# ConMicSchem.net
KiCad netlist of a schematic drawn in Altium Designer
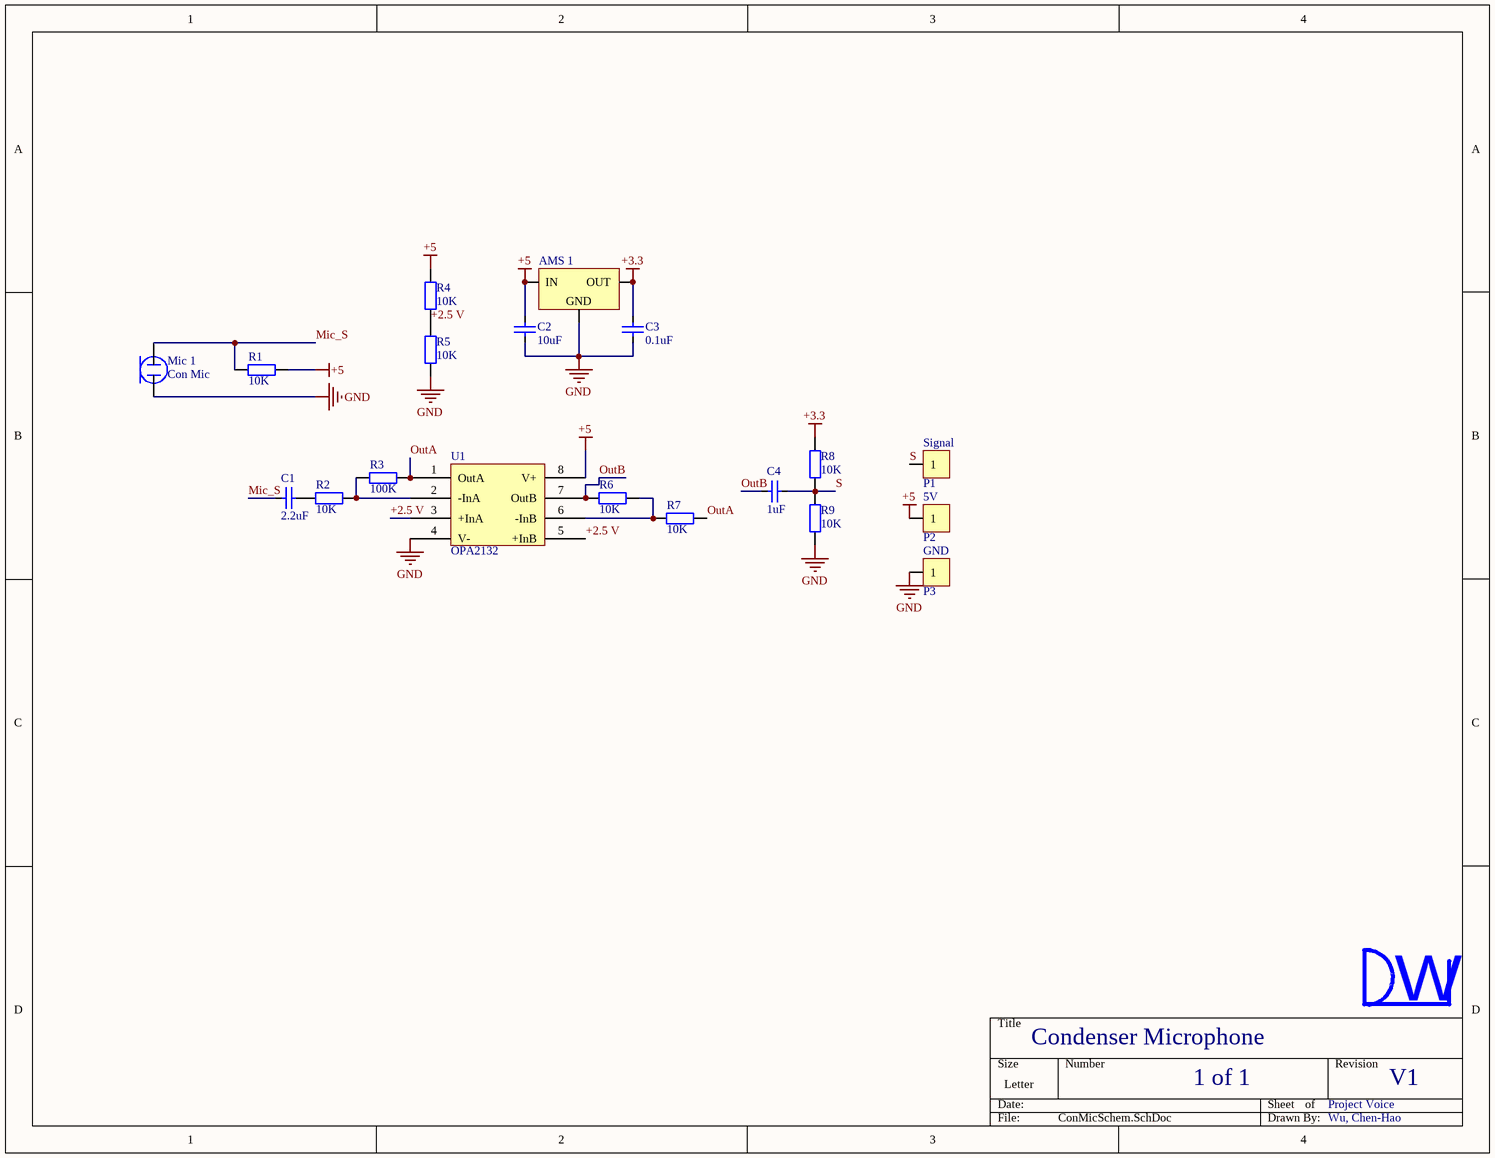
[diagram p0: ConMicSchem.SchDoc]

(export (version "E")
  (design (tool "Eeschema 10.0.6"))
  (components
    (comp (ref "*") (value "DHW_MARK") (libsource (lib "SCH_Mark") (part "DHW_MARK")))
    (comp (ref "AMS 1")
      (value "AMS1117")
      (footprint "PCB_IC:SOT223")
      (description "Power")
      (libsource (lib "SCH_IC") (part "AMS1117"))
    )
    (comp (ref "C1")
      (value "2.2uF")
      (footprint "PCB_Passive:CAP_0603")
      (description "Capacitor")
      (fields (field (name "Comment") "Cap_0603"))
      (libsource (lib "SCH_Passive") (part "Cap_0603"))
    )
    (comp (ref "C2")
      (value "10uF")
      (footprint "PCB_Passive:CAP_0603")
      (description "Capacitor")
      (fields (field (name "Comment") "Cap_0603"))
      (libsource (lib "SCH_Passive") (part "Cap_0603"))
    )
    (comp (ref "C3")
      (value "0.1uF")
      (footprint "PCB_Passive:CAP_0603")
      (description "Capacitor")
      (fields (field (name "Comment") "Cap_0603"))
      (libsource (lib "SCH_Passive") (part "Cap_0603"))
    )
    (comp (ref "C4")
      (value "1uF")
      (footprint "PCB_Passive:CAP_0603")
      (description "Capacitor")
      (fields (field (name "Comment") "Cap_0603"))
      (libsource (lib "SCH_Passive") (part "Cap_0603"))
    )
    (comp (ref "Mic 1")
      (value "Con Mic")
      (footprint "Con_Mic_9.6mm")
      (description "Condenser Microphone")
      (libsource (lib "SCH_Passive") (part "Con_Mic_9.7mm"))
    )
    (comp (ref "P1")
      (value "Signal")
      (footprint "PCB_Connector:HDR1X1_180_2.54")
      (description "Header")
      (libsource (lib "SCH_Connector") (part "HDR1X1_180_2.54"))
    )
    (comp (ref "P2")
      (value "5V")
      (footprint "PCB_Connector:HDR1X1_180_2.54")
      (description "Header")
      (libsource (lib "SCH_Connector") (part "HDR1X1_180_2.54"))
    )
    (comp (ref "P3")
      (value "GND")
      (footprint "PCB_Connector:HDR1X1_180_2.54")
      (description "Header")
      (libsource (lib "SCH_Connector") (part "HDR1X1_180_2.54"))
    )
    (comp (ref "R1")
      (value "10K")
      (footprint "PCB_Passive:RES_0603")
      (description "Resistor")
      (fields (field (name "Comment") "Res_0603"))
      (libsource (lib "SCH_Passive") (part "Res_0603"))
    )
    (comp (ref "R2")
      (value "10K")
      (footprint "PCB_Passive:RES_0603")
      (description "Resistor")
      (fields (field (name "Comment") "Res_0603"))
      (libsource (lib "SCH_Passive") (part "Res_0603"))
    )
    (comp (ref "R3")
      (value "100K")
      (footprint "PCB_Passive:RES_0603")
      (description "Resistor")
      (fields (field (name "Comment") "Res_0603"))
      (libsource (lib "SCH_Passive") (part "Res_0603"))
    )
    (comp (ref "R4")
      (value "10K")
      (footprint "PCB_Passive:RES_0603")
      (description "Resistor")
      (fields (field (name "Comment") "Res_0603"))
      (libsource (lib "") (part "Res_0603_1"))
    )
    (comp (ref "R5")
      (value "10K")
      (footprint "PCB_Passive:RES_0603")
      (description "Resistor")
      (fields (field (name "Comment") "Res_0603"))
      (libsource (lib "") (part "Res_0603_1"))
    )
    (comp (ref "R6")
      (value "10K")
      (footprint "PCB_Passive:RES_0603")
      (description "Resistor")
      (fields (field (name "Comment") "Res_0603"))
      (libsource (lib "SCH_Passive") (part "Res_0603"))
    )
    (comp (ref "R7")
      (value "10K")
      (footprint "PCB_Passive:RES_0603")
      (description "Resistor")
      (fields (field (name "Comment") "Res_0603"))
      (libsource (lib "SCH_Passive") (part "Res_0603"))
    )
    (comp (ref "R8")
      (value "10K")
      (footprint "PCB_Passive:RES_0603")
      (description "Resistor")
      (fields (field (name "Comment") "Res_0603"))
      (libsource (lib "") (part "Res_0603_1"))
    )
    (comp (ref "R9")
      (value "10K")
      (footprint "PCB_Passive:RES_0603")
      (description "Resistor")
      (fields (field (name "Comment") "Res_0603"))
      (libsource (lib "") (part "Res_0603_1"))
    )
    (comp (ref "U1")
      (value "OPA2132")
      (footprint "DIP_8")
      (description "TI BB OPA2132 - 2 op amps IC")
      (libsource (lib "SCH_IC") (part "OPA2132"))
    )
  )
  (nets
    (net (code "1") (name "+3.3") (class "Default")
      (node (ref "AMS 1") (pin "2") (pinfunction "OUT_2") (pintype "power_in"))
      (node (ref "C3") (pin "2") (pinfunction "2_2") (pintype "passive"))
      (node (ref "R8") (pin "2") (pinfunction "2_2") (pintype "passive"))
    )
    (net (code "2") (name "+5") (class "Default")
      (node (ref "AMS 1") (pin "3") (pinfunction "IN_3") (pintype "power_in"))
      (node (ref "C2") (pin "2") (pinfunction "2_2") (pintype "passive"))
      (node (ref "P2") (pin "1") (pinfunction "1_1") (pintype "passive"))
      (node (ref "R1") (pin "2") (pinfunction "2_2") (pintype "passive"))
      (node (ref "R4") (pin "2") (pinfunction "2_2") (pintype "passive"))
      (node (ref "U1") (pin "8") (pinfunction "V+_8") (pintype "passive"))
    )
    (net (code "3") (name "/+2.5 V") (class "Default")
      (node (ref "R4") (pin "1") (pinfunction "1_1") (pintype "passive"))
      (node (ref "R5") (pin "2") (pinfunction "2_2") (pintype "passive"))
      (node (ref "U1") (pin "3") (pinfunction "+InA_3") (pintype "passive"))
      (node (ref "U1") (pin "5") (pinfunction "+InB_5") (pintype "passive"))
    )
    (net (code "4") (name "/Mic_S") (class "Default")
      (node (ref "C1") (pin "1") (pinfunction "1_1") (pintype "passive"))
      (node (ref "Mic 1") (pin "1") (pinfunction "FlexiblePlat_1") (pintype "passive"))
      (node (ref "R1") (pin "1") (pinfunction "1_1") (pintype "passive"))
    )
    (net (code "5") (name "/OutA") (class "Default")
      (node (ref "R3") (pin "2") (pinfunction "2_2") (pintype "passive"))
      (node (ref "R7") (pin "2") (pinfunction "2_2") (pintype "passive"))
      (node (ref "U1") (pin "1") (pinfunction "OutA_1") (pintype "passive"))
    )
    (net (code "6") (name "/OutB") (class "Default")
      (node (ref "C4") (pin "2") (pinfunction "2_2") (pintype "passive"))
      (node (ref "R6") (pin "1") (pinfunction "1_1") (pintype "passive"))
      (node (ref "U1") (pin "7") (pinfunction "OutB_7") (pintype "passive"))
    )
    (net (code "7") (name "/S") (class "Default")
      (node (ref "C4") (pin "1") (pinfunction "1_1") (pintype "passive"))
      (node (ref "P1") (pin "1") (pinfunction "1_1") (pintype "passive"))
      (node (ref "R8") (pin "1") (pinfunction "1_1") (pintype "passive"))
      (node (ref "R9") (pin "2") (pinfunction "2_2") (pintype "passive"))
    )
    (net (code "8") (name "GND") (class "Default")
      (node (ref "AMS 1") (pin "1") (pinfunction "GND_1") (pintype "power_in"))
      (node (ref "C2") (pin "1") (pinfunction "1_1") (pintype "passive"))
      (node (ref "C3") (pin "1") (pinfunction "1_1") (pintype "passive"))
      (node (ref "Mic 1") (pin "2") (pinfunction "RigidPlat_2") (pintype "passive"))
      (node (ref "P3") (pin "1") (pinfunction "1_1") (pintype "passive"))
      (node (ref "R5") (pin "1") (pinfunction "1_1") (pintype "passive"))
      (node (ref "R9") (pin "1") (pinfunction "1_1") (pintype "passive"))
      (node (ref "U1") (pin "4") (pinfunction "V-_4") (pintype "passive"))
    )
    (net (code "9") (name "Net-(C1-Pad2)") (class "Default")
      (node (ref "C1") (pin "2") (pinfunction "2_2") (pintype "passive"))
      (node (ref "R2") (pin "1") (pinfunction "1_1") (pintype "passive"))
    )
    (net (code "10") (name "Net-(U1--InA)") (class "Default")
      (node (ref "R2") (pin "2") (pinfunction "2_2") (pintype "passive"))
      (node (ref "R3") (pin "1") (pinfunction "1_1") (pintype "passive"))
      (node (ref "U1") (pin "2") (pinfunction "-InA_2") (pintype "passive"))
    )
    (net (code "11") (name "Net-(U1--InB)") (class "Default")
      (node (ref "R6") (pin "2") (pinfunction "2_2") (pintype "passive"))
      (node (ref "R7") (pin "1") (pinfunction "1_1") (pintype "passive"))
      (node (ref "U1") (pin "6") (pinfunction "-InB_6") (pintype "passive"))
    )
  )
)
